# Wi-Fi_BT.net
KiCad netlist of a schematic drawn in Altium Designer
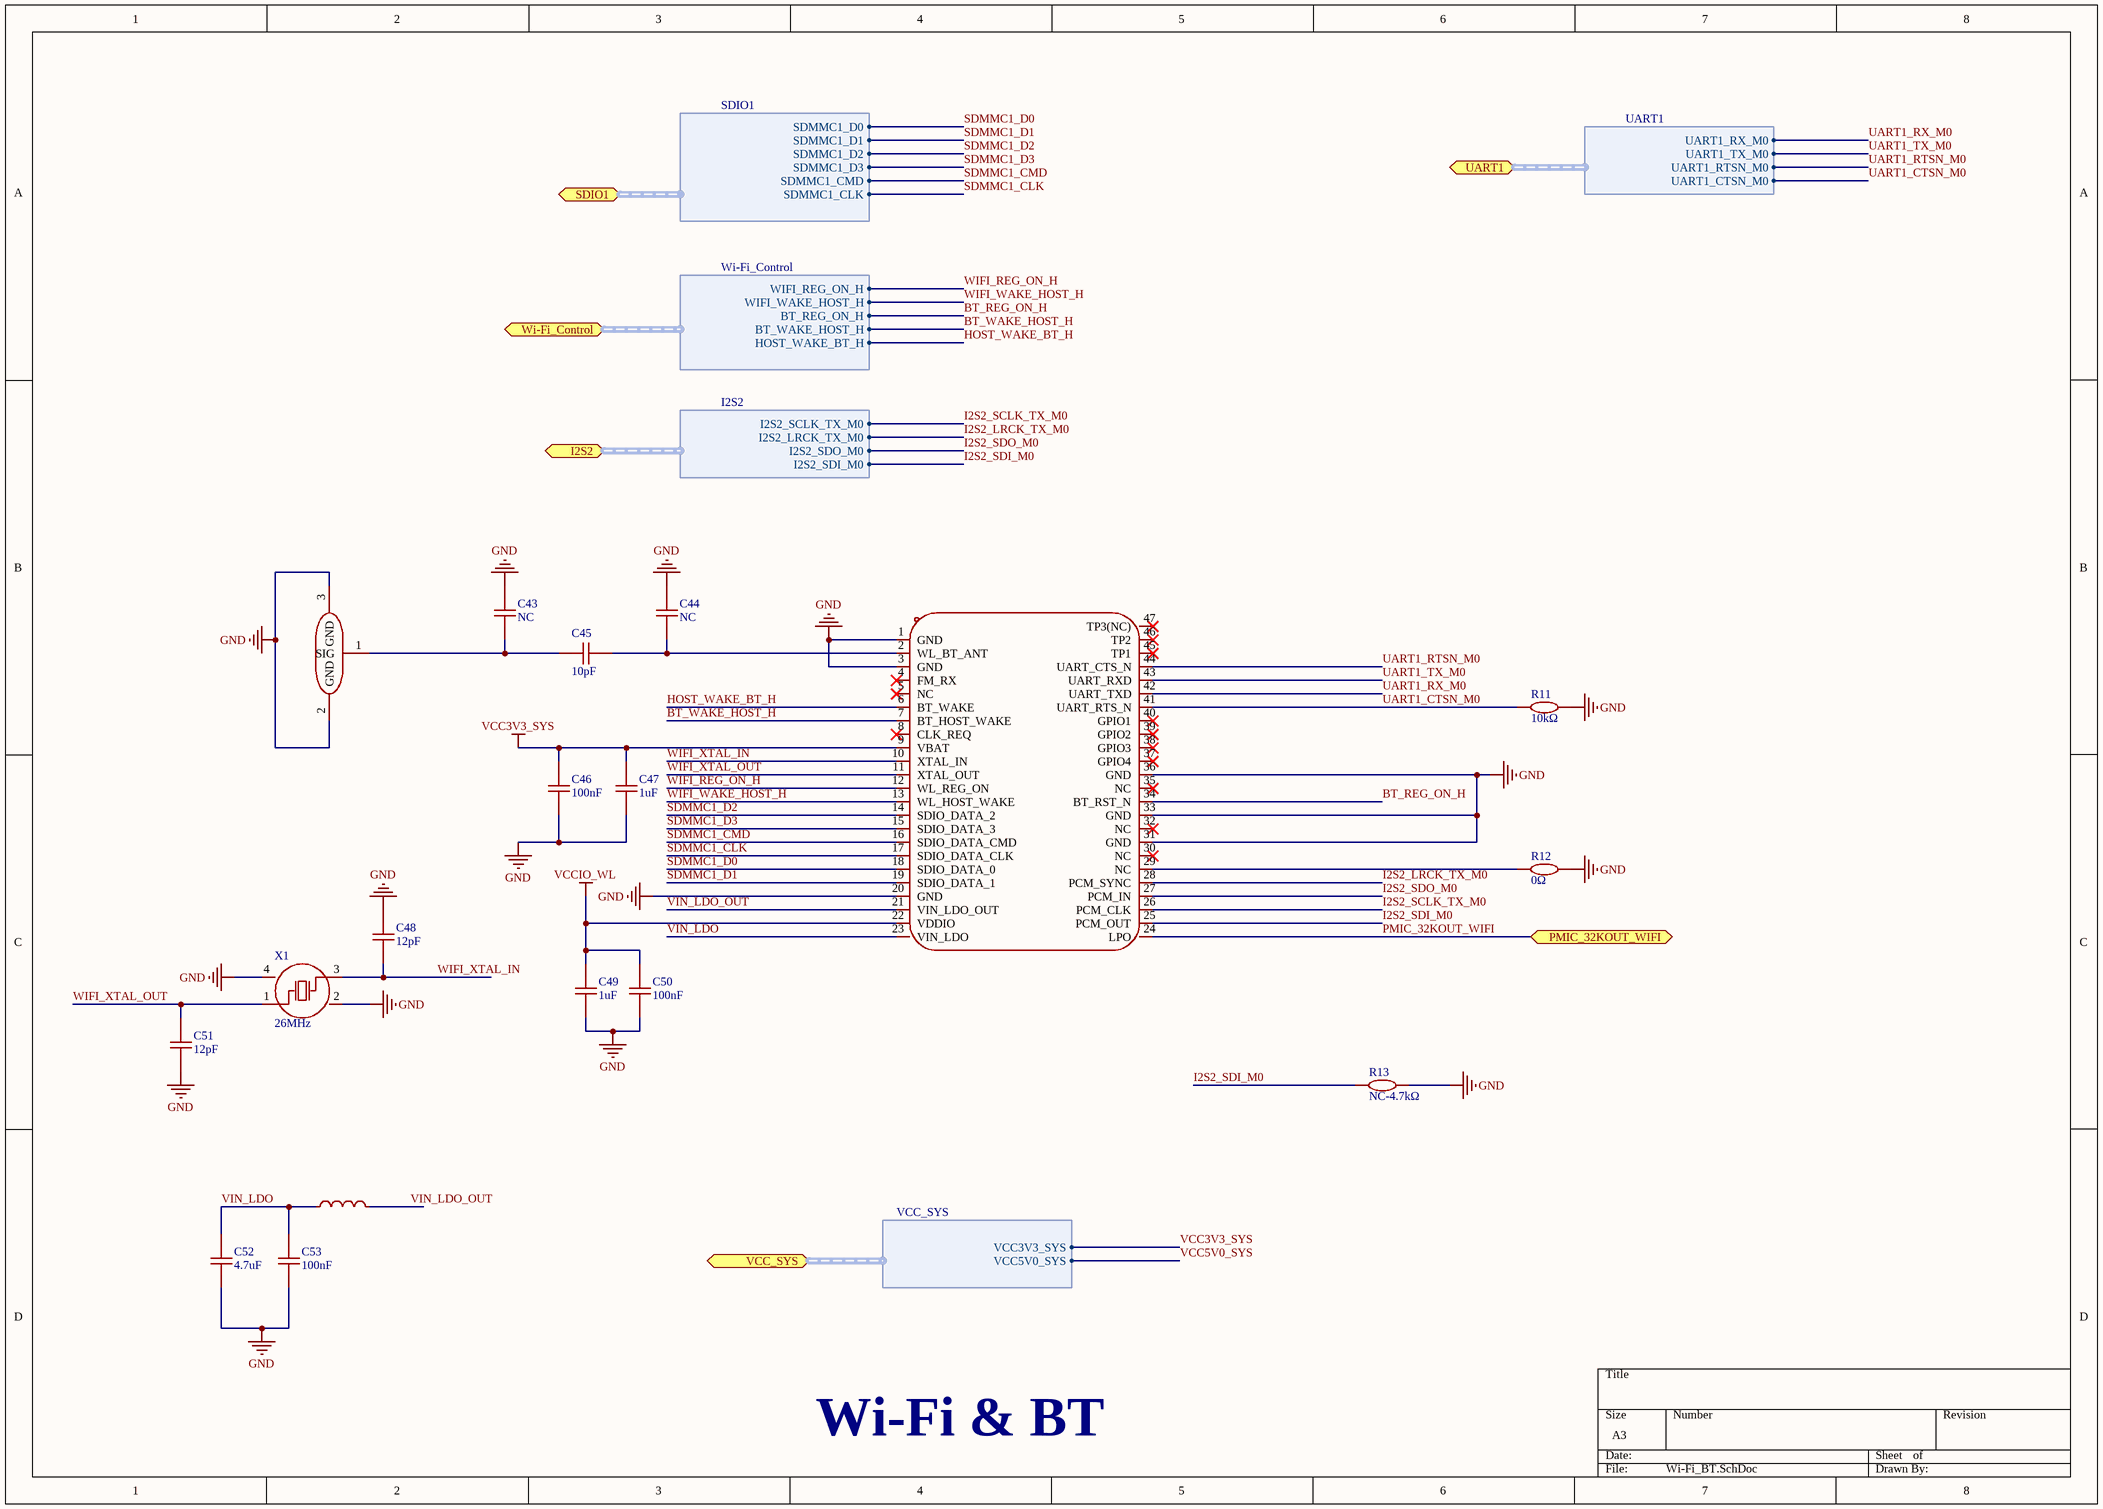
[diagram p0: Wi-Fi_BT.SchDoc]

(export (version "E")
  (design (tool "Eeschema 10.0.6"))
  (components
    (comp (ref "C43")
      (value "NC")
      (footprint "C0402")
      (description "50V 1nF X7R ±10% 0402 Ceramic Capacitors ROHS")
      (libsource (lib "RLC") (part "1nF"))
    )
    (comp (ref "C44")
      (value "NC")
      (footprint "C0402")
      (description "50V 1nF X7R ±10% 0402 Ceramic Capacitors ROHS")
      (libsource (lib "RLC") (part "1nF"))
    )
    (comp (ref "C45")
      (value "10pF")
      (footprint "C0402")
      (description "50V 10pF C0G ±5% 0402 Ceramic Capacitors ROHS")
      (libsource (lib "RLC") (part "10pF"))
    )
    (comp (ref "C46")
      (value "100nF")
      (footprint "C0402")
      (description "50V 100nF X7R ±10% 0402 Ceramic Capacitors ROHS")
      (libsource (lib "RLC") (part "100nF"))
    )
    (comp (ref "C47")
      (value "1uF")
      (footprint "C0402")
      (description "50V 1uF X5R ±10% 0402 Ceramic Capacitors ROHS")
      (libsource (lib "RLC") (part "1uF"))
    )
    (comp (ref "C48")
      (value "12pF")
      (footprint "C0402")
      (description "50V 12pF C0G ±5% 0402 Ceramic Capacitors ROHS")
      (libsource (lib "RLC") (part "12pF"))
    )
    (comp (ref "C49")
      (value "1uF")
      (footprint "C0402")
      (description "50V 1uF X5R ±10% 0402 Ceramic Capacitors ROHS")
      (libsource (lib "RLC") (part "1uF"))
    )
    (comp (ref "C50")
      (value "100nF")
      (footprint "C0402")
      (description "50V 100nF X7R ±10% 0402 Ceramic Capacitors ROHS")
      (libsource (lib "RLC") (part "100nF"))
    )
    (comp (ref "C51")
      (value "12pF")
      (footprint "C0402")
      (description "50V 12pF C0G ±5% 0402 Ceramic Capacitors ROHS")
      (libsource (lib "RLC") (part "12pF"))
    )
    (comp (ref "C52")
      (value "4.7uF")
      (footprint "C0402")
      (description "10V 4.7uF X5R ±20% 0402 Ceramic Capacitors ROHS")
      (libsource (lib "RLC") (part "4.7uF"))
    )
    (comp (ref "C53")
      (value "100nF")
      (footprint "C0402")
      (description "50V 100nF X7R ±10% 0402 Ceramic Capacitors ROHS")
      (libsource (lib "RLC") (part "100nF"))
    )
    (comp (ref "JP1")
      (value "6GHz")
      (footprint "RF-SMD_FRF05002-JSS103M")
      (fields (field (name "MANUFACTURER") "HRS(广濑)") (field (name "MANUFACTURER PART") "U.FL-R-SMT-1(80)"))
      (libsource (lib "Connector") (part "U.FL-R-SMT-1(80)_C88374"))
    )
    (comp (ref "L1")
      (value "4.7uH")
      (footprint "L1008")
      (description "SMD 1008 4.7uH ±20%")
      (fields
        (field (name "MANUFACTURER") "Sunltech(顺磁)")
        (field (name "MANUFACTURER PART") "SLW4030S1R0NST")
      )
      (libsource (lib "RLC") (part "MLP2520S4R7MT0S1"))
    )
    (comp (ref "R11")
      (value "10kΩ")
      (footprint "R0402")
      (description "62.5mW 10kΩ 50V ±100ppm/℃ Thick Film Resistor ±1% 0402 Chip Resistor - Surface Mount ROHS")
      (libsource (lib "RLC") (part "10kΩ"))
    )
    (comp (ref "R12")
      (value "0Ω")
      (footprint "R0402")
      (description "0Ω 62.5mW 50V Thick Film Resistor ±1% 0402 Chip Resistor - Surface Mount ROHS")
      (libsource (lib "RLC") (part "0Ω"))
    )
    (comp (ref "R13")
      (value "NC-4.7kΩ")
      (footprint "R0402")
      (description "5.1kΩ 62.5mW 50V ±100ppm/℃ Thick Film Resistor ±1% 0402 Chip Resistor - Surface Mount ROHS")
      (libsource (lib "RLC") (part "5.1kΩ"))
    )
    (comp (ref "U12")
      (value "2.4GHz")
      (footprint "QFN-44_L12.0-W12.0-P0.90-TL_AP6212")
      (description "2.4GHz -90dBm QFN-44(12x12) RF Transceiver Modules and Modems ROHS")
      (fields (field (name "MANUFACTURER") "AMPAK(正基科技)") (field (name "MANUFACTURER PART") "AP6212"))
      (libsource (lib "IC") (part "AP6212"))
    )
    (comp (ref "X1")
      (value "26MHz")
      (footprint "CRYSTAL-SMD_4P-L2.0-W1.6-BL")
      (description "Q22FA12800230 26MHz ±10ppm 10pF")
      (libsource (lib "OSC") (part "Q22FA12800230"))
    )
  )
  (nets
    (net (code "6") (name "/BT_REG_ON_H") (class "Default")
      (node (ref "U12") (pin "34") (pinfunction "BT_RST_N_34") (pintype "passive"))
    )
    (net (code "7") (name "/BT_WAKE_HOST_H") (class "Default")
      (node (ref "U12") (pin "7") (pinfunction "BT_HOST_WAKE_7") (pintype "passive"))
    )
    (net (code "8") (name "/HOST_WAKE_BT_H") (class "Default")
      (node (ref "U12") (pin "6") (pinfunction "BT_WAKE_6") (pintype "passive"))
    )
    (net (code "9") (name "/I2S2_LRCK_TX_M0") (class "Default")
      (node (ref "U12") (pin "28") (pinfunction "PCM_SYNC_28") (pintype "passive"))
    )
    (net (code "10") (name "/I2S2_SCLK_TX_M0") (class "Default")
      (node (ref "U12") (pin "26") (pinfunction "PCM_CLK_26") (pintype "passive"))
    )
    (net (code "11") (name "/I2S2_SDI_M0") (class "Default")
      (node (ref "R13") (pin "1") (pinfunction "1_1") (pintype "passive"))
      (node (ref "U12") (pin "25") (pinfunction "PCM_OUT_25") (pintype "passive"))
    )
    (net (code "12") (name "/I2S2_SDO_M0") (class "Default")
      (node (ref "U12") (pin "27") (pinfunction "PCM_IN_27") (pintype "passive"))
    )
    (net (code "13") (name "/PMIC_32KOUT_WIFI") (class "Default")
      (node (ref "U12") (pin "24") (pinfunction "LPO_24") (pintype "passive"))
    )
    (net (code "14") (name "/SDMMC1_CLK") (class "Default")
      (node (ref "U12") (pin "17") (pinfunction "SDIO_DATA_CLK_17") (pintype "passive"))
    )
    (net (code "15") (name "/SDMMC1_CMD") (class "Default")
      (node (ref "U12") (pin "16") (pinfunction "SDIO_DATA_CMD_16") (pintype "passive"))
    )
    (net (code "16") (name "/SDMMC1_D0") (class "Default")
      (node (ref "U12") (pin "18") (pinfunction "SDIO_DATA_0_18") (pintype "passive"))
    )
    (net (code "17") (name "/SDMMC1_D1") (class "Default")
      (node (ref "U12") (pin "19") (pinfunction "SDIO_DATA_1_19") (pintype "passive"))
    )
    (net (code "18") (name "/SDMMC1_D2") (class "Default")
      (node (ref "U12") (pin "14") (pinfunction "SDIO_DATA_2_14") (pintype "passive"))
    )
    (net (code "19") (name "/SDMMC1_D3") (class "Default")
      (node (ref "U12") (pin "15") (pinfunction "SDIO_DATA_3_15") (pintype "passive"))
    )
    (net (code "20") (name "/UART1_CTSN_M0") (class "Default")
      (node (ref "R11") (pin "1") (pinfunction "1_1") (pintype "passive"))
      (node (ref "U12") (pin "41") (pinfunction "UART_RTS_N_41") (pintype "passive"))
    )
    (net (code "21") (name "/UART1_RTSN_M0") (class "Default")
      (node (ref "U12") (pin "44") (pinfunction "UART_CTS_N_44") (pintype "passive"))
    )
    (net (code "22") (name "/UART1_RX_M0") (class "Default")
      (node (ref "U12") (pin "42") (pinfunction "UART_TXD_42") (pintype "passive"))
    )
    (net (code "23") (name "/UART1_TX_M0") (class "Default")
      (node (ref "U12") (pin "43") (pinfunction "UART_RXD_43") (pintype "passive"))
    )
    (net (code "25") (name "/VIN_LDO") (class "Default")
      (node (ref "C52") (pin "2") (pinfunction "2_2") (pintype "passive"))
      (node (ref "C53") (pin "2") (pinfunction "2_2") (pintype "passive"))
      (node (ref "L1") (pin "1") (pinfunction "1_1") (pintype "passive"))
      (node (ref "U12") (pin "23") (pinfunction "VIN_LDO_23") (pintype "passive"))
    )
    (net (code "26") (name "/VIN_LDO_OUT") (class "Default")
      (node (ref "L1") (pin "2") (pinfunction "2_2") (pintype "passive"))
      (node (ref "U12") (pin "21") (pinfunction "VIN_LDO_OUT_21") (pintype "passive"))
    )
    (net (code "27") (name "/WIFI_REG_ON_H") (class "Default")
      (node (ref "U12") (pin "12") (pinfunction "WL_REG_ON_12") (pintype "passive"))
    )
    (net (code "28") (name "/WIFI_WAKE_HOST_H") (class "Default")
      (node (ref "U12") (pin "13") (pinfunction "WL_HOST_WAKE_13") (pintype "passive"))
    )
    (net (code "29") (name "/WIFI_XTAL_IN") (class "Default")
      (node (ref "C48") (pin "1") (pinfunction "1_1") (pintype "passive"))
      (node (ref "U12") (pin "10") (pinfunction "XTAL_IN_10") (pintype "passive"))
      (node (ref "X1") (pin "3") (pinfunction "OSC2_3") (pintype "passive"))
    )
    (net (code "30") (name "/WIFI_XTAL_OUT") (class "Default")
      (node (ref "C51") (pin "2") (pinfunction "2_2") (pintype "passive"))
      (node (ref "U12") (pin "11") (pinfunction "XTAL_OUT_11") (pintype "passive"))
      (node (ref "X1") (pin "1") (pinfunction "OSC1_1") (pintype "passive"))
    )
    (net (code "36") (name "GND") (class "Default")
      (node (ref "C43") (pin "2") (pinfunction "2_2") (pintype "passive"))
      (node (ref "C44") (pin "2") (pinfunction "2_2") (pintype "passive"))
      (node (ref "C46") (pin "1") (pinfunction "1_1") (pintype "passive"))
      (node (ref "C47") (pin "1") (pinfunction "1_1") (pintype "passive"))
      (node (ref "C48") (pin "2") (pinfunction "2_2") (pintype "passive"))
      (node (ref "C49") (pin "1") (pinfunction "1_1") (pintype "passive"))
      (node (ref "C50") (pin "1") (pinfunction "1_1") (pintype "passive"))
      (node (ref "C51") (pin "1") (pinfunction "1_1") (pintype "passive"))
      (node (ref "C52") (pin "1") (pinfunction "1_1") (pintype "passive"))
      (node (ref "C53") (pin "1") (pinfunction "1_1") (pintype "passive"))
      (node (ref "JP1") (pin "2") (pinfunction "GND_2") (pintype "passive"))
      (node (ref "JP1") (pin "3") (pinfunction "GND_3") (pintype "passive"))
      (node (ref "R11") (pin "2") (pinfunction "2_2") (pintype "passive"))
      (node (ref "R12") (pin "2") (pinfunction "2_2") (pintype "passive"))
      (node (ref "R13") (pin "2") (pinfunction "2_2") (pintype "passive"))
      (node (ref "U12") (pin "1") (pinfunction "GND_1") (pintype "passive"))
      (node (ref "U12") (pin "20") (pinfunction "GND_20") (pintype "passive"))
      (node (ref "U12") (pin "3") (pinfunction "GND_3") (pintype "passive"))
      (node (ref "U12") (pin "31") (pinfunction "GND_31") (pintype "passive"))
      (node (ref "U12") (pin "33") (pinfunction "GND_33") (pintype "passive"))
      (node (ref "U12") (pin "36") (pinfunction "GND_36") (pintype "passive"))
      (node (ref "X1") (pin "2") (pinfunction "GND_2") (pintype "passive"))
      (node (ref "X1") (pin "4") (pinfunction "GND_4") (pintype "passive"))
    )
    (net (code "37") (name "Net-(JP1-SIG)") (class "Default")
      (node (ref "C43") (pin "1") (pinfunction "1_1") (pintype "passive"))
      (node (ref "C45") (pin "1") (pinfunction "1_1") (pintype "passive"))
      (node (ref "JP1") (pin "1") (pinfunction "SIG_1") (pintype "passive"))
    )
    (net (code "38") (name "Net-(R12-Pad1)") (class "Default")
      (node (ref "R12") (pin "1") (pinfunction "1_1") (pintype "passive"))
      (node (ref "U12") (pin "29") (pinfunction "NC_29") (pintype "passive"))
    )
    (net (code "39") (name "Net-(U12-WL_BT_ANT)") (class "Default")
      (node (ref "C44") (pin "1") (pinfunction "1_1") (pintype "passive"))
      (node (ref "C45") (pin "2") (pinfunction "2_2") (pintype "passive"))
      (node (ref "U12") (pin "2") (pinfunction "WL_BT_ANT_2") (pintype "passive"))
    )
    (net (code "40") (name "VCC3V3_SYS") (class "Default")
      (node (ref "C46") (pin "2") (pinfunction "2_2") (pintype "passive"))
      (node (ref "C47") (pin "2") (pinfunction "2_2") (pintype "passive"))
      (node (ref "U12") (pin "9") (pinfunction "VBAT_9") (pintype "passive"))
    )
    (net (code "41") (name "VCCIO_WL") (class "Default")
      (node (ref "C49") (pin "2") (pinfunction "2_2") (pintype "passive"))
      (node (ref "C50") (pin "2") (pinfunction "2_2") (pintype "passive"))
      (node (ref "U12") (pin "22") (pinfunction "VDDIO_22") (pintype "passive"))
    )
    (net (code "42") (name "unconnected-(U12-CLK_REQ-Pad8)") (class "Default")
      (node (ref "U12") (pin "8") (pinfunction "CLK_REQ_8") (pintype "passive+no_connect"))
    )
    (net (code "43") (name "unconnected-(U12-FM_RX-Pad4)") (class "Default")
      (node (ref "U12") (pin "4") (pinfunction "FM_RX_4") (pintype "passive+no_connect"))
    )
    (net (code "44") (name "unconnected-(U12-GPIO1-Pad40)") (class "Default")
      (node (ref "U12") (pin "40") (pinfunction "GPIO1_40") (pintype "passive+no_connect"))
    )
    (net (code "45") (name "unconnected-(U12-GPIO2-Pad39)") (class "Default")
      (node (ref "U12") (pin "39") (pinfunction "GPIO2_39") (pintype "passive+no_connect"))
    )
    (net (code "46") (name "unconnected-(U12-GPIO3-Pad38)") (class "Default")
      (node (ref "U12") (pin "38") (pinfunction "GPIO3_38") (pintype "passive+no_connect"))
    )
    (net (code "47") (name "unconnected-(U12-GPIO4-Pad37)") (class "Default")
      (node (ref "U12") (pin "37") (pinfunction "GPIO4_37") (pintype "passive+no_connect"))
    )
    (net (code "48") (name "unconnected-(U12-NC-Pad5)") (class "Default")
      (node (ref "U12") (pin "5") (pinfunction "NC_5") (pintype "passive+no_connect"))
    )
    (net (code "49") (name "unconnected-(U12-NC-Pad30)") (class "Default")
      (node (ref "U12") (pin "30") (pinfunction "NC_30") (pintype "passive+no_connect"))
    )
    (net (code "50") (name "unconnected-(U12-NC-Pad32)") (class "Default")
      (node (ref "U12") (pin "32") (pinfunction "NC_32") (pintype "passive+no_connect"))
    )
    (net (code "51") (name "unconnected-(U12-NC-Pad35)") (class "Default")
      (node (ref "U12") (pin "35") (pinfunction "NC_35") (pintype "passive+no_connect"))
    )
    (net (code "52") (name "unconnected-(U12-TP1-Pad45)") (class "Default")
      (node (ref "U12") (pin "45") (pinfunction "TP1_45") (pintype "passive+no_connect"))
    )
    (net (code "53") (name "unconnected-(U12-TP2-Pad46)") (class "Default")
      (node (ref "U12") (pin "46") (pinfunction "TP2_46") (pintype "passive+no_connect"))
    )
    (net (code "54") (name "unconnected-(U12-TP3(NC)-Pad47)") (class "Default")
      (node (ref "U12") (pin "47") (pinfunction "TP3(NC)_47") (pintype "passive+no_connect"))
    )
  )
)
